# Msi001.net
KiCad netlist of a schematic drawn in Altium Designer
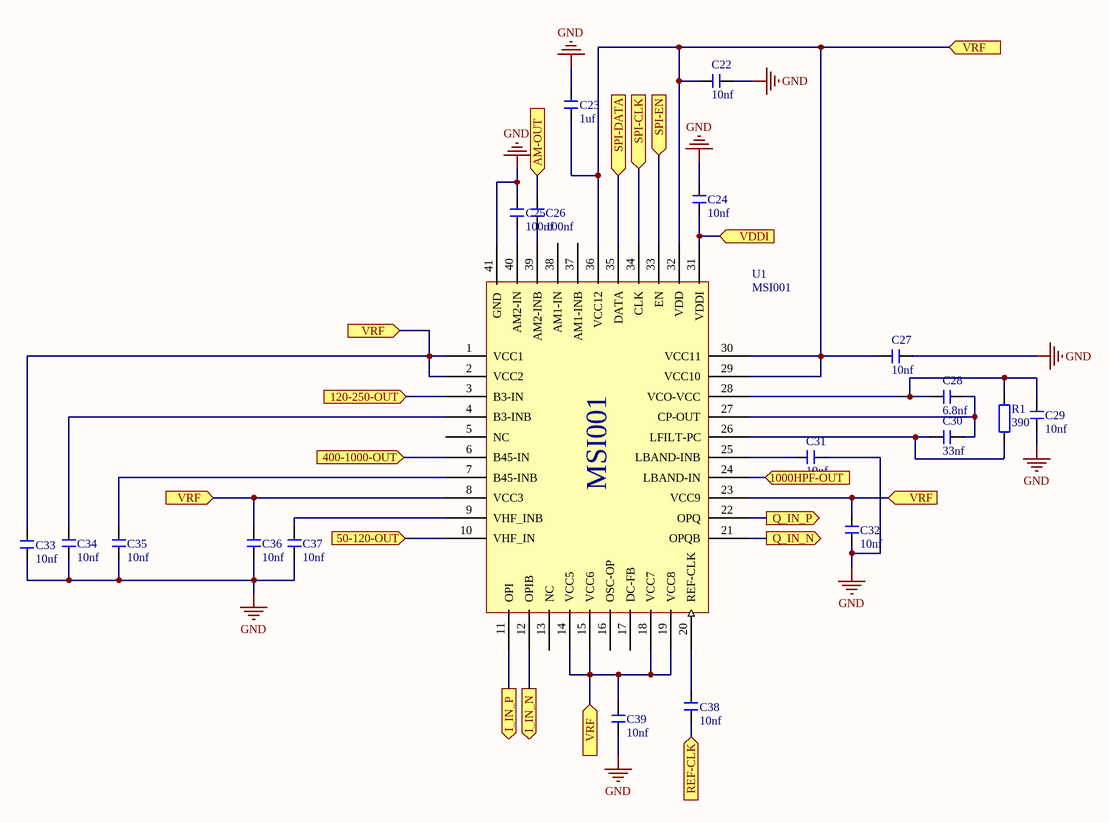
[diagram p0: Msi001.SchDoc]

(export (version "E")
  (design (tool "Eeschema 10.0.6"))
  (components
    (comp (ref "C22")
      (value "10nf")
      (footprint "C 0603_M")
      (description "无极性贴片电容")
      (fields (field (name "版权归属") "源创客"))
      (libsource (lib "电阻-电容-电感") (part "C"))
    )
    (comp (ref "C23")
      (value "1uf")
      (footprint "C 0603_M")
      (description "无极性贴片电容")
      (fields (field (name "版权归属") "源创客"))
      (libsource (lib "电阻-电容-电感") (part "C"))
    )
    (comp (ref "C24")
      (value "10nf")
      (footprint "C 0603_M")
      (description "无极性贴片电容")
      (fields (field (name "版权归属") "源创客"))
      (libsource (lib "电阻-电容-电感") (part "C"))
    )
    (comp (ref "C25")
      (value "100nf")
      (footprint "C 0603_M")
      (description "无极性贴片电容")
      (fields (field (name "版权归属") "源创客"))
      (libsource (lib "电阻-电容-电感") (part "C"))
    )
    (comp (ref "C26")
      (value "100nf")
      (footprint "C 0603_M")
      (description "无极性贴片电容")
      (fields (field (name "版权归属") "源创客"))
      (libsource (lib "电阻-电容-电感") (part "C"))
    )
    (comp (ref "C27")
      (value "10nf")
      (footprint "C 0603_M")
      (description "无极性贴片电容")
      (fields (field (name "版权归属") "源创客"))
      (libsource (lib "电阻-电容-电感") (part "C"))
    )
    (comp (ref "C28")
      (value "6.8nf")
      (footprint "C 0603_M")
      (description "无极性贴片电容")
      (fields (field (name "版权归属") "源创客"))
      (libsource (lib "电阻-电容-电感") (part "C"))
    )
    (comp (ref "C29")
      (value "10nf")
      (footprint "C 0603_M")
      (description "无极性贴片电容")
      (fields (field (name "版权归属") "源创客"))
      (libsource (lib "电阻-电容-电感") (part "C"))
    )
    (comp (ref "C30")
      (value "33nf")
      (footprint "C 0603_M")
      (description "无极性贴片电容")
      (fields (field (name "版权归属") "源创客"))
      (libsource (lib "电阻-电容-电感") (part "C"))
    )
    (comp (ref "C31")
      (value "10nf")
      (footprint "C 0603_M")
      (description "无极性贴片电容")
      (fields (field (name "版权归属") "源创客"))
      (libsource (lib "电阻-电容-电感") (part "C"))
    )
    (comp (ref "C32")
      (value "10nf")
      (footprint "C 0603_M")
      (description "无极性贴片电容")
      (fields (field (name "版权归属") "源创客"))
      (libsource (lib "电阻-电容-电感") (part "C"))
    )
    (comp (ref "C33")
      (value "10nf")
      (footprint "C 0603_M")
      (description "无极性贴片电容")
      (fields (field (name "版权归属") "源创客"))
      (libsource (lib "电阻-电容-电感") (part "C"))
    )
    (comp (ref "C34")
      (value "10nf")
      (footprint "C 0603_M")
      (description "无极性贴片电容")
      (fields (field (name "版权归属") "源创客"))
      (libsource (lib "电阻-电容-电感") (part "C"))
    )
    (comp (ref "C35")
      (value "10nf")
      (footprint "C 0603_M")
      (description "无极性贴片电容")
      (fields (field (name "版权归属") "源创客"))
      (libsource (lib "电阻-电容-电感") (part "C"))
    )
    (comp (ref "C36")
      (value "10nf")
      (footprint "C 0603_M")
      (description "无极性贴片电容")
      (fields (field (name "版权归属") "源创客"))
      (libsource (lib "电阻-电容-电感") (part "C"))
    )
    (comp (ref "C37")
      (value "10nf")
      (footprint "C 0603_M")
      (description "无极性贴片电容")
      (fields (field (name "版权归属") "源创客"))
      (libsource (lib "电阻-电容-电感") (part "C"))
    )
    (comp (ref "C38")
      (value "10nf")
      (footprint "C 0603_M")
      (description "无极性贴片电容")
      (fields (field (name "版权归属") "源创客"))
      (libsource (lib "电阻-电容-电感") (part "C"))
    )
    (comp (ref "C39")
      (value "10nf")
      (footprint "C 0603_M")
      (description "无极性贴片电容")
      (fields (field (name "版权归属") "源创客"))
      (libsource (lib "电阻-电容-电感") (part "C"))
    )
    (comp (ref "R1")
      (value "390")
      (footprint "R 0603_M")
      (description "贴片电阻")
      (fields (field (name "版权归属") "源创客"))
      (libsource (lib "电阻-电容-电感") (part "R"))
    )
    (comp (ref "U1")
      (value "MSI001")
      (footprint "QFN40 6X6_M")
      (description "tuner")
      (libsource (lib "IC芯片") (part "MSI001"))
    )
  )
  (nets
    (net (code "1") (name "/50-120-OUT") (class "Default")
      (node (ref "U1") (pin "10") (pinfunction "VHF_IN_10") (pintype "passive"))
    )
    (net (code "2") (name "/120-250-OUT") (class "Default")
      (node (ref "U1") (pin "3") (pinfunction "B3-IN_3") (pintype "passive"))
    )
    (net (code "3") (name "/400-1000-OUT") (class "Default")
      (node (ref "U1") (pin "6") (pinfunction "B45-IN_6") (pintype "passive"))
    )
    (net (code "4") (name "/1000HPF-OUT") (class "Default")
      (node (ref "U1") (pin "24") (pinfunction "LBAND-IN_24") (pintype "passive"))
    )
    (net (code "5") (name "/AM-OUT") (class "Default")
      (node (ref "C26") (pin "2") (pinfunction "2_2") (pintype "passive"))
    )
    (net (code "6") (name "/I_IN_N") (class "Default")
      (node (ref "U1") (pin "12") (pinfunction "OPIB_12") (pintype "passive"))
    )
    (net (code "7") (name "/I_IN_P") (class "Default")
      (node (ref "U1") (pin "11") (pinfunction "OPI_11") (pintype "passive"))
    )
    (net (code "8") (name "/Q_IN_N") (class "Default")
      (node (ref "U1") (pin "21") (pinfunction "OPQB_21") (pintype "passive"))
    )
    (net (code "9") (name "/Q_IN_P") (class "Default")
      (node (ref "U1") (pin "22") (pinfunction "OPQ_22") (pintype "passive"))
    )
    (net (code "10") (name "/REF-CLK") (class "Default")
      (node (ref "C38") (pin "2") (pinfunction "2_2") (pintype "passive"))
    )
    (net (code "11") (name "/SPI-CLK") (class "Default")
      (node (ref "U1") (pin "34") (pinfunction "CLK_34") (pintype "passive"))
    )
    (net (code "12") (name "/SPI-DATA") (class "Default")
      (node (ref "U1") (pin "35") (pinfunction "DATA_35") (pintype "passive"))
    )
    (net (code "13") (name "/SPI-EN") (class "Default")
      (node (ref "U1") (pin "33") (pinfunction "EN_33") (pintype "passive"))
    )
    (net (code "14") (name "/VDDI") (class "Default")
      (node (ref "C24") (pin "1") (pinfunction "1_1") (pintype "passive"))
      (node (ref "U1") (pin "31") (pinfunction "VDDI_31") (pintype "passive"))
    )
    (net (code "15") (name "/VRF") (class "Default")
      (node (ref "C22") (pin "2") (pinfunction "2_2") (pintype "passive"))
      (node (ref "C23") (pin "1") (pinfunction "1_1") (pintype "passive"))
      (node (ref "C27") (pin "2") (pinfunction "2_2") (pintype "passive"))
      (node (ref "C32") (pin "1") (pinfunction "1_1") (pintype "passive"))
      (node (ref "C33") (pin "2") (pinfunction "2_2") (pintype "passive"))
      (node (ref "C36") (pin "2") (pinfunction "2_2") (pintype "passive"))
      (node (ref "C39") (pin "1") (pinfunction "1_1") (pintype "passive"))
      (node (ref "U1") (pin "1") (pinfunction "VCC1_1") (pintype "passive"))
      (node (ref "U1") (pin "14") (pinfunction "VCC5_14") (pintype "passive"))
      (node (ref "U1") (pin "15") (pinfunction "VCC6_15") (pintype "passive"))
      (node (ref "U1") (pin "18") (pinfunction "VCC7_18") (pintype "passive"))
      (node (ref "U1") (pin "19") (pinfunction "VCC8_19") (pintype "passive"))
      (node (ref "U1") (pin "2") (pinfunction "VCC2_2") (pintype "passive"))
      (node (ref "U1") (pin "23") (pinfunction "VCC9_23") (pintype "passive"))
      (node (ref "U1") (pin "29") (pinfunction "VCC10_29") (pintype "passive"))
      (node (ref "U1") (pin "30") (pinfunction "VCC11_30") (pintype "passive"))
      (node (ref "U1") (pin "32") (pinfunction "VDD_32") (pintype "passive"))
      (node (ref "U1") (pin "36") (pinfunction "VCC12_36") (pintype "passive"))
      (node (ref "U1") (pin "8") (pinfunction "VCC3_8") (pintype "passive"))
    )
    (net (code "16") (name "GND") (class "Default")
      (node (ref "C22") (pin "1") (pinfunction "1_1") (pintype "passive"))
      (node (ref "C23") (pin "2") (pinfunction "2_2") (pintype "passive"))
      (node (ref "C24") (pin "2") (pinfunction "2_2") (pintype "passive"))
      (node (ref "C25") (pin "2") (pinfunction "2_2") (pintype "passive"))
      (node (ref "C27") (pin "1") (pinfunction "1_1") (pintype "passive"))
      (node (ref "C29") (pin "2") (pinfunction "2_2") (pintype "passive"))
      (node (ref "C31") (pin "2") (pinfunction "2_2") (pintype "passive"))
      (node (ref "C32") (pin "2") (pinfunction "2_2") (pintype "passive"))
      (node (ref "C33") (pin "1") (pinfunction "1_1") (pintype "passive"))
      (node (ref "C34") (pin "1") (pinfunction "1_1") (pintype "passive"))
      (node (ref "C35") (pin "2") (pinfunction "2_2") (pintype "passive"))
      (node (ref "C36") (pin "1") (pinfunction "1_1") (pintype "passive"))
      (node (ref "C37") (pin "1") (pinfunction "1_1") (pintype "passive"))
      (node (ref "C39") (pin "2") (pinfunction "2_2") (pintype "passive"))
      (node (ref "U1") (pin "41") (pinfunction "GND_41") (pintype "passive"))
    )
    (net (code "17") (name "Net-(U1-AM2-IN)") (class "Default")
      (node (ref "C25") (pin "1") (pinfunction "1_1") (pintype "passive"))
      (node (ref "U1") (pin "40") (pinfunction "AM2-IN_40") (pintype "passive"))
    )
    (net (code "18") (name "Net-(U1-AM2-INB)") (class "Default")
      (node (ref "C26") (pin "1") (pinfunction "1_1") (pintype "passive"))
      (node (ref "U1") (pin "39") (pinfunction "AM2-INB_39") (pintype "passive"))
    )
    (net (code "19") (name "Net-(U1-B3-INB)") (class "Default")
      (node (ref "C34") (pin "2") (pinfunction "2_2") (pintype "passive"))
      (node (ref "U1") (pin "4") (pinfunction "B3-INB_4") (pintype "passive"))
    )
    (net (code "20") (name "Net-(U1-B45-INB)") (class "Default")
      (node (ref "C35") (pin "1") (pinfunction "1_1") (pintype "passive"))
      (node (ref "U1") (pin "7") (pinfunction "B45-INB_7") (pintype "passive"))
    )
    (net (code "21") (name "Net-(U1-CP-OUT)") (class "Default")
      (node (ref "C28") (pin "1") (pinfunction "1_1") (pintype "passive"))
      (node (ref "C30") (pin "1") (pinfunction "1_1") (pintype "passive"))
      (node (ref "U1") (pin "27") (pinfunction "CP-OUT_27") (pintype "passive"))
    )
    (net (code "22") (name "Net-(U1-LBAND-INB)") (class "Default")
      (node (ref "C31") (pin "1") (pinfunction "1_1") (pintype "passive"))
      (node (ref "U1") (pin "25") (pinfunction "LBAND-INB_25") (pintype "passive"))
    )
    (net (code "23") (name "Net-(U1-LFILT-PC)") (class "Default")
      (node (ref "C30") (pin "2") (pinfunction "2_2") (pintype "passive"))
      (node (ref "R1") (pin "2") (pinfunction "2_2") (pintype "passive"))
      (node (ref "U1") (pin "26") (pinfunction "LFILT-PC_26") (pintype "passive"))
    )
    (net (code "24") (name "Net-(U1-REF-CLK)") (class "Default")
      (node (ref "C38") (pin "1") (pinfunction "1_1") (pintype "passive"))
      (node (ref "U1") (pin "20") (pinfunction "REF-CLK_20") (pintype "input"))
    )
    (net (code "25") (name "Net-(U1-VCO-VCC)") (class "Default")
      (node (ref "C28") (pin "2") (pinfunction "2_2") (pintype "passive"))
      (node (ref "C29") (pin "1") (pinfunction "1_1") (pintype "passive"))
      (node (ref "R1") (pin "1") (pinfunction "1_1") (pintype "passive"))
      (node (ref "U1") (pin "28") (pinfunction "VCO-VCC_28") (pintype "passive"))
    )
    (net (code "26") (name "Net-(U1-VHF_INB)") (class "Default")
      (node (ref "C37") (pin "2") (pinfunction "2_2") (pintype "passive"))
      (node (ref "U1") (pin "9") (pinfunction "VHF_INB_9") (pintype "passive"))
    )
    (net (code "27") (name "unconnected-(U1-AM1-IN-Pad38)") (class "Default")
      (node (ref "U1") (pin "38") (pinfunction "AM1-IN_38") (pintype "passive"))
    )
    (net (code "28") (name "unconnected-(U1-AM1-INB-Pad37)") (class "Default")
      (node (ref "U1") (pin "37") (pinfunction "AM1-INB_37") (pintype "passive"))
    )
    (net (code "29") (name "unconnected-(U1-DC-FB-Pad17)") (class "Default")
      (node (ref "U1") (pin "17") (pinfunction "DC-FB_17") (pintype "passive"))
    )
    (net (code "30") (name "unconnected-(U1-NC-Pad5)") (class "Default")
      (node (ref "U1") (pin "5") (pinfunction "NC_5") (pintype "passive"))
    )
    (net (code "31") (name "unconnected-(U1-NC-Pad13)") (class "Default")
      (node (ref "U1") (pin "13") (pinfunction "NC_13") (pintype "passive"))
    )
    (net (code "32") (name "unconnected-(U1-OSC-OP-Pad16)") (class "Default")
      (node (ref "U1") (pin "16") (pinfunction "OSC-OP_16") (pintype "passive"))
    )
  )
)
